# chariot_comms_a.net
KiCad netlist of a schematic drawn in EAGLE
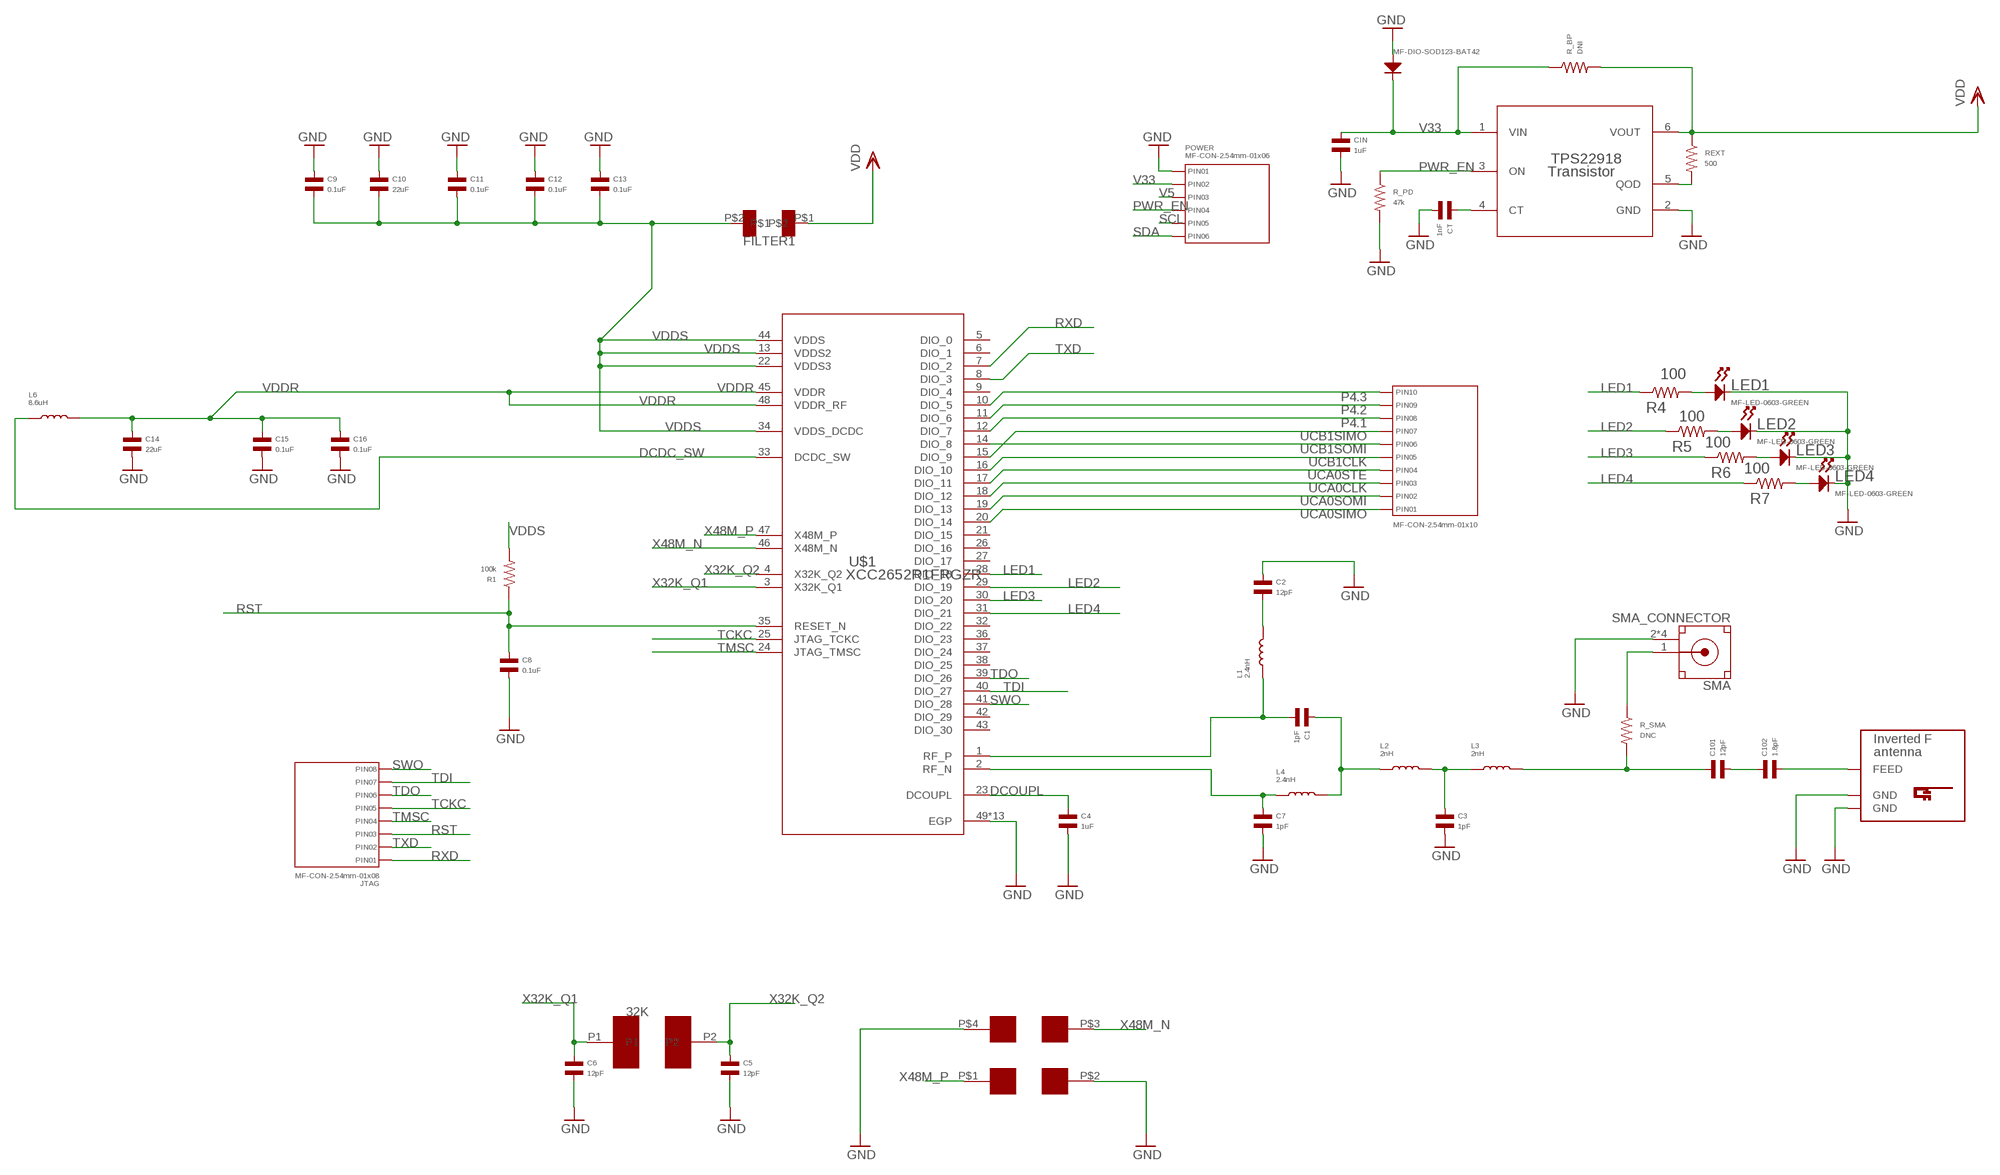
[diagram p0: schematic, sheet 1]

(export (version "E")
  (design (tool "Eeschema 10.0.6"))
  (components
    (comp (ref "32K")
      (value "FC-135")
      (footprint "eagle-import:FC-135")
      (libsource (lib "eagle-import") (part "FC-135"))
    )
    (comp (ref "48M")
      (value "NX2016SA-48M-EXS00A-CS05517")
      (footprint "eagle-import:NX2016SA-48M-EXS00A-CS05517")
      (libsource (lib "eagle-import") (part "NX2016SA-48M-EXS00A-CS05517"))
    )
    (comp (ref "C1")
      (value "1pF")
      (footprint "eagle-import:C0603")
      (libsource (lib "eagle-import") (part "CAPACITOR_NP_0603"))
    )
    (comp (ref "C2")
      (value "12pF")
      (footprint "eagle-import:C0603")
      (libsource (lib "eagle-import") (part "CAPACITOR_NP_0603"))
    )
    (comp (ref "C3")
      (value "1pF")
      (footprint "eagle-import:C0603")
      (libsource (lib "eagle-import") (part "CAPACITOR_NP_0603"))
    )
    (comp (ref "C4")
      (value "1uF")
      (footprint "eagle-import:C0603")
      (libsource (lib "eagle-import") (part "CAPACITOR_NP_0603"))
    )
    (comp (ref "C5")
      (value "12pF")
      (footprint "eagle-import:C0603")
      (libsource (lib "eagle-import") (part "CAPACITOR_NP_0603"))
    )
    (comp (ref "C6")
      (value "12pF")
      (footprint "eagle-import:C0603")
      (libsource (lib "eagle-import") (part "CAPACITOR_NP_0603"))
    )
    (comp (ref "C7")
      (value "1pF")
      (footprint "eagle-import:C0603")
      (libsource (lib "eagle-import") (part "CAPACITOR_NP_0603"))
    )
    (comp (ref "C8")
      (value "0.1uF")
      (footprint "eagle-import:C0603")
      (libsource (lib "eagle-import") (part "CAPACITOR_NP_0603"))
    )
    (comp (ref "C9")
      (value "0.1uF")
      (footprint "eagle-import:C0603")
      (libsource (lib "eagle-import") (part "CAPACITOR_NP_0603"))
    )
    (comp (ref "C10")
      (value "22uF")
      (footprint "eagle-import:C0603")
      (libsource (lib "eagle-import") (part "CAPACITOR_NP_0603"))
    )
    (comp (ref "C11")
      (value "0.1uF")
      (footprint "eagle-import:C0603")
      (libsource (lib "eagle-import") (part "CAPACITOR_NP_0603"))
    )
    (comp (ref "C12")
      (value "0.1uF")
      (footprint "eagle-import:C0603")
      (libsource (lib "eagle-import") (part "CAPACITOR_NP_0603"))
    )
    (comp (ref "C13")
      (value "0.1uF")
      (footprint "eagle-import:C0603")
      (libsource (lib "eagle-import") (part "CAPACITOR_NP_0603"))
    )
    (comp (ref "C14")
      (value "22uF")
      (footprint "eagle-import:C0603")
      (libsource (lib "eagle-import") (part "CAPACITOR_NP_0603"))
    )
    (comp (ref "C15")
      (value "0.1uF")
      (footprint "eagle-import:C0603")
      (libsource (lib "eagle-import") (part "CAPACITOR_NP_0603"))
    )
    (comp (ref "C16")
      (value "0.1uF")
      (footprint "eagle-import:C0603")
      (libsource (lib "eagle-import") (part "CAPACITOR_NP_0603"))
    )
    (comp (ref "C101")
      (value "12pF")
      (footprint "eagle-import:C0603")
      (libsource (lib "eagle-import") (part "CAPACITOR_NP_0603"))
    )
    (comp (ref "C102")
      (value "1.8pF")
      (footprint "eagle-import:C0603")
      (libsource (lib "eagle-import") (part "CAPACITOR_NP_0603"))
    )
    (comp (ref "CIN")
      (value "1uF")
      (footprint "eagle-import:C0603")
      (libsource (lib "eagle-import") (part "CAPACITOR_NP_0603"))
    )
    (comp (ref "COMMS_J")
      (value "MF-CON-2.54mm-01x10")
      (footprint "eagle-import:PTH_2.54MM_01X10")
      (fields (field (name "HOUSEPART") "YES"))
      (libsource (lib "eagle-import") (part "CON_01X10_PTH_2.54MM"))
    )
    (comp (ref "CT")
      (value "1nF")
      (footprint "eagle-import:C0603")
      (libsource (lib "eagle-import") (part "CAPACITOR_NP_0603"))
    )
    (comp (ref "D1")
      (value "MF-DIO-SOD123-BAT42")
      (footprint "eagle-import:SOD-123")
      (fields (field (name "HOUSEPART") "YES"))
      (libsource (lib "eagle-import") (part "DIODES_SOD-123_BAT42"))
    )
    (comp (ref "FILTER1")
      (value "BLM18HE152SN1D")
      (footprint "eagle-import:BLM18HE152SN1D")
      (libsource (lib "eagle-import") (part "BLM18HE152SN1D"))
    )
    (comp (ref "JTAG")
      (value "MF-CON-2.54mm-01x08")
      (footprint "eagle-import:PTH_2.54MM_01X08")
      (fields (field (name "HOUSEPART") "YES"))
      (libsource (lib "eagle-import") (part "CON_01X08_PTH_2.54MM"))
    )
    (comp (ref "L1")
      (value "2.4nH")
      (footprint "eagle-import:L0603")
      (libsource (lib "eagle-import") (part "INDUCTOR_0603"))
    )
    (comp (ref "L2")
      (value "2nH")
      (footprint "eagle-import:L0603")
      (libsource (lib "eagle-import") (part "INDUCTOR_0603"))
    )
    (comp (ref "L3")
      (value "2nH")
      (footprint "eagle-import:L0603")
      (libsource (lib "eagle-import") (part "INDUCTOR_0603"))
    )
    (comp (ref "L4")
      (value "2.4nH")
      (footprint "eagle-import:L0603")
      (libsource (lib "eagle-import") (part "INDUCTOR_0603"))
    )
    (comp (ref "L6")
      (value "8.6uH")
      (footprint "eagle-import:L0603")
      (libsource (lib "eagle-import") (part "INDUCTOR_0603"))
    )
    (comp (ref "LED1")
      (value "MF-LED-0603-GREEN")
      (footprint "eagle-import:LED0603")
      (fields (field (name "HOUSEPART") "YES"))
      (libsource (lib "eagle-import") (part "LED_SINGLE-0603-GREEN"))
    )
    (comp (ref "LED2")
      (value "MF-LED-0603-GREEN")
      (footprint "eagle-import:LED0603")
      (fields (field (name "HOUSEPART") "YES"))
      (libsource (lib "eagle-import") (part "LED_SINGLE-0603-GREEN"))
    )
    (comp (ref "LED3")
      (value "MF-LED-0603-GREEN")
      (footprint "eagle-import:LED0603")
      (fields (field (name "HOUSEPART") "YES"))
      (libsource (lib "eagle-import") (part "LED_SINGLE-0603-GREEN"))
    )
    (comp (ref "LED4")
      (value "MF-LED-0603-GREEN")
      (footprint "eagle-import:LED0603")
      (fields (field (name "HOUSEPART") "YES"))
      (libsource (lib "eagle-import") (part "LED_SINGLE-0603-GREEN"))
    )
    (comp (ref "POWER")
      (value "MF-CON-2.54mm-01x06")
      (footprint "eagle-import:PTH_2.54MM_01X06")
      (fields (field (name "HOUSEPART") "YES"))
      (libsource (lib "eagle-import") (part "CON_01X06_PTH_2.54MM"))
    )
    (comp (ref "R1")
      (value "100k")
      (footprint "eagle-import:R0603")
      (libsource (lib "eagle-import") (part "RESISTOR_0603"))
    )
    (comp (ref "R4")
      (value "100")
      (footprint "eagle-import:R0603")
      (libsource (lib "eagle-import") (part "RESISTOR_0603"))
    )
    (comp (ref "R5")
      (value "100")
      (footprint "eagle-import:R0603")
      (libsource (lib "eagle-import") (part "RESISTOR_0603"))
    )
    (comp (ref "R6")
      (value "100")
      (footprint "eagle-import:R0603")
      (libsource (lib "eagle-import") (part "RESISTOR_0603"))
    )
    (comp (ref "R7")
      (value "100")
      (footprint "eagle-import:R0603")
      (libsource (lib "eagle-import") (part "RESISTOR_0603"))
    )
    (comp (ref "REXT")
      (value "500")
      (footprint "eagle-import:R0603")
      (libsource (lib "eagle-import") (part "RESISTOR_0603"))
    )
    (comp (ref "R_BP")
      (value "DNI")
      (footprint "eagle-import:R0603")
      (libsource (lib "eagle-import") (part "RESISTOR_0603"))
    )
    (comp (ref "R_PD")
      (value "47k")
      (footprint "eagle-import:R0603")
      (libsource (lib "eagle-import") (part "RESISTOR_0603"))
    )
    (comp (ref "R_SMA")
      (value "DNC")
      (footprint "eagle-import:R0603")
      (libsource (lib "eagle-import") (part "RESISTOR_0603"))
    )
    (comp (ref "SMA")
      (value "SMA_CONNECTOR")
      (footprint "eagle-import:LPRS_SMA_CONNECTOR")
      (fields (field (name "MF") "LPRS") (field (name "MP") "SMA CONNECTOR"))
      (libsource (lib "eagle-import") (part "SMA_CONNECTOR"))
    )
    (comp (ref "TPS22918")
      (value "Transistor")
      (footprint "eagle-import:DBV0006A_N")
      (fields (field (name "MANUFACTURER") "Texas Instruments") (field (name "PARTNUMBER") "TPS22918TDBVRQ1"))
      (libsource (lib "eagle-import") (part "TPS22918TDBVRQ1"))
    )
    (comp (ref "U$1")
      (value "XCC2652R1FRGZR")
      (footprint "eagle-import:RGZ0048A")
      (libsource (lib "eagle-import") (part "XCC2652R1FRGZR"))
    )
    (comp (ref "U$2")
      (value "INVERTED_F_ANTENNA+5")
      (footprint "eagle-import:DN007+5")
      (libsource (lib "eagle-import") (part "INVERTED_F_ANTENNA+5"))
    )
  )
  (nets
    (net (code "1") (name "/DCDC_SW") (class "Default")
      (node (ref "L6") (pin "P$1") (pinfunction "P$1_P$1") (pintype "passive"))
      (node (ref "U$1") (pin "33") (pinfunction "DCDC_SW_33") (pintype "power_in"))
    )
    (net (code "2") (name "/DCOUPL") (class "Default")
      (node (ref "C4") (pin "P$1") (pinfunction "P$1_P$1") (pintype "passive"))
      (node (ref "U$1") (pin "23") (pinfunction "DCOUPL_23") (pintype "power_in"))
    )
    (net (code "3") (name "/LED1") (class "Default")
      (node (ref "R4") (pin "P$1") (pinfunction "P$1_P$1") (pintype "passive"))
      (node (ref "U$1") (pin "28") (pinfunction "DIO_18_28") (pintype "bidirectional"))
    )
    (net (code "4") (name "/LED2") (class "Default")
      (node (ref "R5") (pin "P$1") (pinfunction "P$1_P$1") (pintype "passive"))
      (node (ref "U$1") (pin "29") (pinfunction "DIO_19_29") (pintype "bidirectional"))
    )
    (net (code "5") (name "/LED3") (class "Default")
      (node (ref "R6") (pin "P$1") (pinfunction "P$1_P$1") (pintype "passive"))
      (node (ref "U$1") (pin "30") (pinfunction "DIO_20_30") (pintype "bidirectional"))
    )
    (net (code "6") (name "/LED4") (class "Default")
      (node (ref "R7") (pin "P$1") (pinfunction "P$1_P$1") (pintype "passive"))
      (node (ref "U$1") (pin "31") (pinfunction "DIO_21_31") (pintype "bidirectional"))
    )
    (net (code "7") (name "/P4.1") (class "Default")
      (node (ref "COMMS_J") (pin "P$8") (pinfunction "PIN8_P$8") (pintype "bidirectional"))
      (node (ref "U$1") (pin "12") (pinfunction "DIO_7_12") (pintype "bidirectional"))
    )
    (net (code "8") (name "/P4.2") (class "Default")
      (node (ref "COMMS_J") (pin "P$9") (pinfunction "PIN9_P$9") (pintype "bidirectional"))
      (node (ref "U$1") (pin "11") (pinfunction "DIO_6_11") (pintype "bidirectional"))
    )
    (net (code "9") (name "/P4.3") (class "Default")
      (node (ref "COMMS_J") (pin "P$10") (pinfunction "PIN10_P$10") (pintype "bidirectional"))
      (node (ref "U$1") (pin "10") (pinfunction "DIO_5_10") (pintype "bidirectional"))
    )
    (net (code "10") (name "/PWR_EN") (class "Default")
      (node (ref "POWER") (pin "P$4") (pinfunction "PIN4_P$4") (pintype "bidirectional"))
      (node (ref "R_PD") (pin "P$1") (pinfunction "P$1_P$1") (pintype "passive"))
      (node (ref "TPS22918") (pin "3") (pinfunction "ON_3") (pintype "input"))
    )
    (net (code "11") (name "/RST") (class "Default")
      (node (ref "C8") (pin "P$1") (pinfunction "P$1_P$1") (pintype "passive"))
      (node (ref "JTAG") (pin "P$3") (pinfunction "PIN3_P$3") (pintype "bidirectional"))
      (node (ref "R1") (pin "P$1") (pinfunction "P$1_P$1") (pintype "passive"))
      (node (ref "U$1") (pin "35") (pinfunction "RESET_N_35") (pintype "input"))
    )
    (net (code "12") (name "/RXD") (class "Default")
      (node (ref "JTAG") (pin "P$1") (pinfunction "PIN1_P$1") (pintype "bidirectional"))
      (node (ref "U$1") (pin "7") (pinfunction "DIO_2_7") (pintype "bidirectional"))
    )
    (net (code "13") (name "/SCL") (class "Default")
      (node (ref "POWER") (pin "P$5") (pinfunction "PIN5_P$5") (pintype "bidirectional"))
    )
    (net (code "14") (name "/SDA") (class "Default")
      (node (ref "POWER") (pin "P$6") (pinfunction "PIN6_P$6") (pintype "bidirectional"))
    )
    (net (code "15") (name "/SWO") (class "Default")
      (node (ref "JTAG") (pin "P$8") (pinfunction "PIN8_P$8") (pintype "bidirectional"))
      (node (ref "U$1") (pin "41") (pinfunction "DIO_28_41") (pintype "bidirectional"))
    )
    (net (code "16") (name "/TCKC") (class "Default")
      (node (ref "JTAG") (pin "P$5") (pinfunction "PIN5_P$5") (pintype "bidirectional"))
      (node (ref "U$1") (pin "25") (pinfunction "JTAG_TCKC_25") (pintype "bidirectional"))
    )
    (net (code "17") (name "/TDI") (class "Default")
      (node (ref "JTAG") (pin "P$7") (pinfunction "PIN7_P$7") (pintype "bidirectional"))
      (node (ref "U$1") (pin "40") (pinfunction "DIO_27_40") (pintype "bidirectional"))
    )
    (net (code "18") (name "/TDO") (class "Default")
      (node (ref "JTAG") (pin "P$6") (pinfunction "PIN6_P$6") (pintype "bidirectional"))
      (node (ref "U$1") (pin "39") (pinfunction "DIO_26_39") (pintype "bidirectional"))
    )
    (net (code "19") (name "/TMSC") (class "Default")
      (node (ref "JTAG") (pin "P$4") (pinfunction "PIN4_P$4") (pintype "bidirectional"))
      (node (ref "U$1") (pin "24") (pinfunction "JTAG_TMSC_24") (pintype "bidirectional"))
    )
    (net (code "20") (name "/TXD") (class "Default")
      (node (ref "JTAG") (pin "P$2") (pinfunction "PIN2_P$2") (pintype "bidirectional"))
      (node (ref "U$1") (pin "8") (pinfunction "DIO_3_8") (pintype "bidirectional"))
    )
    (net (code "21") (name "/UCA0CLK") (class "Default")
      (node (ref "COMMS_J") (pin "P$3") (pinfunction "PIN3_P$3") (pintype "bidirectional"))
      (node (ref "U$1") (pin "18") (pinfunction "DIO_12_18") (pintype "bidirectional"))
    )
    (net (code "22") (name "/UCA0SIMO") (class "Default")
      (node (ref "COMMS_J") (pin "P$1") (pinfunction "PIN1_P$1") (pintype "bidirectional"))
      (node (ref "U$1") (pin "20") (pinfunction "DIO_14_20") (pintype "bidirectional"))
    )
    (net (code "23") (name "/UCA0SOMI") (class "Default")
      (node (ref "COMMS_J") (pin "P$2") (pinfunction "PIN2_P$2") (pintype "bidirectional"))
      (node (ref "U$1") (pin "19") (pinfunction "DIO_13_19") (pintype "bidirectional"))
    )
    (net (code "24") (name "/UCA0STE") (class "Default")
      (node (ref "COMMS_J") (pin "P$4") (pinfunction "PIN4_P$4") (pintype "bidirectional"))
      (node (ref "U$1") (pin "17") (pinfunction "DIO_11_17") (pintype "bidirectional"))
    )
    (net (code "25") (name "/UCB1CLK") (class "Default")
      (node (ref "COMMS_J") (pin "P$5") (pinfunction "PIN5_P$5") (pintype "bidirectional"))
      (node (ref "U$1") (pin "16") (pinfunction "DIO_10_16") (pintype "bidirectional"))
    )
    (net (code "26") (name "/UCB1SIMO") (class "Default")
      (node (ref "COMMS_J") (pin "P$7") (pinfunction "PIN7_P$7") (pintype "bidirectional"))
      (node (ref "U$1") (pin "15") (pinfunction "DIO_9_15") (pintype "bidirectional"))
    )
    (net (code "27") (name "/UCB1SOMI") (class "Default")
      (node (ref "COMMS_J") (pin "P$6") (pinfunction "PIN6_P$6") (pintype "bidirectional"))
      (node (ref "U$1") (pin "14") (pinfunction "DIO_8_14") (pintype "bidirectional"))
    )
    (net (code "28") (name "/V5") (class "Default")
      (node (ref "POWER") (pin "P$3") (pinfunction "PIN3_P$3") (pintype "bidirectional"))
    )
    (net (code "29") (name "/V33") (class "Default")
      (node (ref "CIN") (pin "P$1") (pinfunction "P$1_P$1") (pintype "passive"))
      (node (ref "D1") (pin "CATHODE") (pinfunction "CATHODE_CATHODE") (pintype "bidirectional"))
      (node (ref "POWER") (pin "P$2") (pinfunction "PIN2_P$2") (pintype "bidirectional"))
      (node (ref "R_BP") (pin "P$1") (pinfunction "P$1_P$1") (pintype "passive"))
      (node (ref "TPS22918") (pin "1") (pinfunction "VIN_1") (pintype "power_in"))
    )
    (net (code "30") (name "/VDDR") (class "Default")
      (node (ref "C14") (pin "P$1") (pinfunction "P$1_P$1") (pintype "passive"))
      (node (ref "C15") (pin "P$1") (pinfunction "P$1_P$1") (pintype "passive"))
      (node (ref "C16") (pin "P$1") (pinfunction "P$1_P$1") (pintype "passive"))
      (node (ref "L6") (pin "P$2") (pinfunction "P$2_P$2") (pintype "passive"))
      (node (ref "U$1") (pin "45") (pinfunction "VDDR_45") (pintype "power_in"))
      (node (ref "U$1") (pin "48") (pinfunction "VDDR_RF_48") (pintype "power_in"))
    )
    (net (code "31") (name "/VDDS") (class "Default")
      (node (ref "C10") (pin "P$2") (pinfunction "P$2_P$2") (pintype "passive"))
      (node (ref "C11") (pin "P$2") (pinfunction "P$2_P$2") (pintype "passive"))
      (node (ref "C12") (pin "P$2") (pinfunction "P$2_P$2") (pintype "passive"))
      (node (ref "C13") (pin "P$2") (pinfunction "P$2_P$2") (pintype "passive"))
      (node (ref "C9") (pin "P$2") (pinfunction "P$2_P$2") (pintype "passive"))
      (node (ref "FILTER1") (pin "P$2") (pinfunction "P$2_P$2") (pintype "bidirectional"))
      (node (ref "R1") (pin "P$2") (pinfunction "P$2_P$2") (pintype "passive"))
      (node (ref "U$1") (pin "13") (pinfunction "VDDS2_13") (pintype "power_in"))
      (node (ref "U$1") (pin "22") (pinfunction "VDDS3_22") (pintype "power_in"))
      (node (ref "U$1") (pin "34") (pinfunction "VDDS_DCDC_34") (pintype "power_in"))
      (node (ref "U$1") (pin "44") (pinfunction "VDDS_44") (pintype "power_in"))
    )
    (net (code "32") (name "/X32K_Q1") (class "Default")
      (node (ref "32K") (pin "P1") (pinfunction "P1_P1") (pintype "bidirectional"))
      (node (ref "C6") (pin "P$1") (pinfunction "P$1_P$1") (pintype "passive"))
      (node (ref "U$1") (pin "3") (pinfunction "X32K_Q1_3") (pintype "bidirectional"))
    )
    (net (code "33") (name "/X32K_Q2") (class "Default")
      (node (ref "32K") (pin "P2") (pinfunction "P2_P2") (pintype "bidirectional"))
      (node (ref "C5") (pin "P$1") (pinfunction "P$1_P$1") (pintype "passive"))
      (node (ref "U$1") (pin "4") (pinfunction "X32K_Q2_4") (pintype "bidirectional"))
    )
    (net (code "34") (name "/X48M_N") (class "Default")
      (node (ref "48M") (pin "P$3") (pinfunction "P$3_P$3") (pintype "bidirectional"))
      (node (ref "U$1") (pin "46") (pinfunction "X48M_N_46") (pintype "bidirectional"))
    )
    (net (code "35") (name "/X48M_P") (class "Default")
      (node (ref "48M") (pin "P$1") (pinfunction "P$1_P$1") (pintype "bidirectional"))
      (node (ref "U$1") (pin "47") (pinfunction "X48M_P_47") (pintype "bidirectional"))
    )
    (net (code "36") (name "GND") (class "Default")
      (node (ref "48M") (pin "P$2") (pinfunction "P$2_P$2") (pintype "bidirectional"))
      (node (ref "48M") (pin "P$4") (pinfunction "P$4_P$4") (pintype "bidirectional"))
      (node (ref "C10") (pin "P$1") (pinfunction "P$1_P$1") (pintype "passive"))
      (node (ref "C11") (pin "P$1") (pinfunction "P$1_P$1") (pintype "passive"))
      (node (ref "C12") (pin "P$1") (pinfunction "P$1_P$1") (pintype "passive"))
      (node (ref "C13") (pin "P$1") (pinfunction "P$1_P$1") (pintype "passive"))
      (node (ref "C14") (pin "P$2") (pinfunction "P$2_P$2") (pintype "passive"))
      (node (ref "C15") (pin "P$2") (pinfunction "P$2_P$2") (pintype "passive"))
      (node (ref "C16") (pin "P$2") (pinfunction "P$2_P$2") (pintype "passive"))
      (node (ref "C2") (pin "P$1") (pinfunction "P$1_P$1") (pintype "passive"))
      (node (ref "C3") (pin "P$2") (pinfunction "P$2_P$2") (pintype "passive"))
      (node (ref "C4") (pin "P$2") (pinfunction "P$2_P$2") (pintype "passive"))
      (node (ref "C5") (pin "P$2") (pinfunction "P$2_P$2") (pintype "passive"))
      (node (ref "C6") (pin "P$2") (pinfunction "P$2_P$2") (pintype "passive"))
      (node (ref "C7") (pin "P$2") (pinfunction "P$2_P$2") (pintype "passive"))
      (node (ref "C8") (pin "P$2") (pinfunction "P$2_P$2") (pintype "passive"))
      (node (ref "C9") (pin "P$1") (pinfunction "P$1_P$1") (pintype "passive"))
      (node (ref "CIN") (pin "P$2") (pinfunction "P$2_P$2") (pintype "passive"))
      (node (ref "CT") (pin "P$2") (pinfunction "P$2_P$2") (pintype "passive"))
      (node (ref "D1") (pin "ANODE") (pinfunction "ANODE_ANODE") (pintype "bidirectional"))
      (node (ref "LED1") (pin "CATHODE") (pinfunction "CATHODE_CATHODE") (pintype "power_in"))
      (node (ref "LED2") (pin "CATHODE") (pinfunction "CATHODE_CATHODE") (pintype "power_in"))
      (node (ref "LED3") (pin "CATHODE") (pinfunction "CATHODE_CATHODE") (pintype "power_in"))
      (node (ref "LED4") (pin "CATHODE") (pinfunction "CATHODE_CATHODE") (pintype "power_in"))
      (node (ref "POWER") (pin "P$1") (pinfunction "PIN1_P$1") (pintype "bidirectional"))
      (node (ref "R_PD") (pin "P$2") (pinfunction "P$2_P$2") (pintype "passive"))
      (node (ref "SMA") (pin "2") (pinfunction "GND_2") (pintype "passive"))
      (node (ref "SMA") (pin "3") (pinfunction "GND_3") (pintype "passive"))
      (node (ref "SMA") (pin "4") (pinfunction "GND_4") (pintype "passive"))
      (node (ref "SMA") (pin "5") (pinfunction "GND_5") (pintype "passive"))
      (node (ref "TPS22918") (pin "2") (pinfunction "GND_2") (pintype "power_in"))
      (node (ref "U$1") (pin "49") (pinfunction "EGP_49") (pintype "power_in"))
      (node (ref "U$1") (pin "V1") (pinfunction "EGP_V1") (pintype "power_in"))
      (node (ref "U$1") (pin "V10") (pinfunction "EGP_V10") (pintype "power_in"))
      (node (ref "U$1") (pin "V11") (pinfunction "EGP_V11") (pintype "power_in"))
      (node (ref "U$1") (pin "V12") (pinfunction "EGP_V12") (pintype "power_in"))
      (node (ref "U$1") (pin "V2") (pinfunction "EGP_V2") (pintype "power_in"))
      (node (ref "U$1") (pin "V3") (pinfunction "EGP_V3") (pintype "power_in"))
      (node (ref "U$1") (pin "V4") (pinfunction "EGP_V4") (pintype "power_in"))
      (node (ref "U$1") (pin "V5") (pinfunction "EGP_V5") (pintype "power_in"))
      (node (ref "U$1") (pin "V6") (pinfunction "EGP_V6") (pintype "power_in"))
      (node (ref "U$1") (pin "V7") (pinfunction "EGP_V7") (pintype "power_in"))
      (node (ref "U$1") (pin "V8") (pinfunction "EGP_V8") (pintype "power_in"))
      (node (ref "U$1") (pin "V9") (pinfunction "EGP_V9") (pintype "power_in"))
      (node (ref "U$2") (pin "GND") (pinfunction "GND_GND") (pintype "bidirectional"))
      (node (ref "U$2") (pin "GND@1") (pinfunction "GND_GND@1") (pintype "bidirectional"))
    )
    (net (code "37") (name "Net-(C1-PadP$1)") (class "Default")
      (node (ref "C1") (pin "P$1") (pinfunction "P$1_P$1") (pintype "passive"))
      (node (ref "L2") (pin "P$1") (pinfunction "P$1_P$1") (pintype "passive"))
      (node (ref "L4") (pin "P$2") (pinfunction "P$2_P$2") (pintype "passive"))
    )
    (net (code "38") (name "Net-(C2-PadP$2)") (class "Default")
      (node (ref "C2") (pin "P$2") (pinfunction "P$2_P$2") (pintype "passive"))
      (node (ref "L1") (pin "P$2") (pinfunction "P$2_P$2") (pintype "passive"))
    )
    (net (code "39") (name "Net-(C3-PadP$1)") (class "Default")
      (node (ref "C3") (pin "P$1") (pinfunction "P$1_P$1") (pintype "passive"))
      (node (ref "L2") (pin "P$2") (pinfunction "P$2_P$2") (pintype "passive"))
      (node (ref "L3") (pin "P$1") (pinfunction "P$1_P$1") (pintype "passive"))
    )
    (net (code "40") (name "Net-(C101-PadP$1)") (class "Default")
      (node (ref "C101") (pin "P$1") (pinfunction "P$1_P$1") (pintype "passive"))
      (node (ref "L3") (pin "P$2") (pinfunction "P$2_P$2") (pintype "passive"))
      (node (ref "R_SMA") (pin "P$2") (pinfunction "P$2_P$2") (pintype "passive"))
    )
    (net (code "41") (name "Net-(C101-PadP$2)") (class "Default")
      (node (ref "C101") (pin "P$2") (pinfunction "P$2_P$2") (pintype "passive"))
      (node (ref "C102") (pin "P$1") (pinfunction "P$1_P$1") (pintype "passive"))
    )
    (net (code "42") (name "Net-(C102-PadP$2)") (class "Default")
      (node (ref "C102") (pin "P$2") (pinfunction "P$2_P$2") (pintype "passive"))
      (node (ref "U$2") (pin "FEED") (pinfunction "FEED_FEED") (pintype "bidirectional"))
    )
    (net (code "43") (name "Net-(LED1-PadANODE)") (class "Default")
      (node (ref "LED1") (pin "ANODE") (pinfunction "ANODE_ANODE") (pintype "power_in"))
      (node (ref "R4") (pin "P$2") (pinfunction "P$2_P$2") (pintype "passive"))
    )
    (net (code "44") (name "Net-(LED2-PadANODE)") (class "Default")
      (node (ref "LED2") (pin "ANODE") (pinfunction "ANODE_ANODE") (pintype "power_in"))
      (node (ref "R5") (pin "P$2") (pinfunction "P$2_P$2") (pintype "passive"))
    )
    (net (code "45") (name "Net-(LED3-PadANODE)") (class "Default")
      (node (ref "LED3") (pin "ANODE") (pinfunction "ANODE_ANODE") (pintype "power_in"))
      (node (ref "R6") (pin "P$2") (pinfunction "P$2_P$2") (pintype "passive"))
    )
    (net (code "46") (name "Net-(LED4-PadANODE)") (class "Default")
      (node (ref "LED4") (pin "ANODE") (pinfunction "ANODE_ANODE") (pintype "power_in"))
      (node (ref "R7") (pin "P$2") (pinfunction "P$2_P$2") (pintype "passive"))
    )
    (net (code "47") (name "Net-(SMA-SIG)") (class "Default")
      (node (ref "R_SMA") (pin "P$1") (pinfunction "P$1_P$1") (pintype "passive"))
      (node (ref "SMA") (pin "1") (pinfunction "SIG_1") (pintype "passive"))
    )
    (net (code "48") (name "Net-(TPS22918-CT)") (class "Default")
      (node (ref "CT") (pin "P$1") (pinfunction "P$1_P$1") (pintype "passive"))
      (node (ref "TPS22918") (pin "4") (pinfunction "CT_4") (pintype "output"))
    )
    (net (code "49") (name "Net-(TPS22918-QOD)") (class "Default")
      (node (ref "REXT") (pin "P$2") (pinfunction "P$2_P$2") (pintype "passive"))
      (node (ref "TPS22918") (pin "5") (pinfunction "QOD_5") (pintype "input"))
    )
    (net (code "50") (name "Net-(U$1-RF_N)") (class "Default")
      (node (ref "C7") (pin "P$1") (pinfunction "P$1_P$1") (pintype "passive"))
      (node (ref "L4") (pin "P$1") (pinfunction "P$1_P$1") (pintype "passive"))
      (node (ref "U$1") (pin "2") (pinfunction "RF_N_2") (pintype "bidirectional"))
    )
    (net (code "51") (name "Net-(U$1-RF_P)") (class "Default")
      (node (ref "C1") (pin "P$2") (pinfunction "P$2_P$2") (pintype "passive"))
      (node (ref "L1") (pin "P$1") (pinfunction "P$1_P$1") (pintype "passive"))
      (node (ref "U$1") (pin "1") (pinfunction "RF_P_1") (pintype "bidirectional"))
    )
    (net (code "52") (name "VDD") (class "Default")
      (node (ref "FILTER1") (pin "P$1") (pinfunction "P$1_P$1") (pintype "bidirectional"))
      (node (ref "REXT") (pin "P$1") (pinfunction "P$1_P$1") (pintype "passive"))
      (node (ref "R_BP") (pin "P$2") (pinfunction "P$2_P$2") (pintype "passive"))
      (node (ref "TPS22918") (pin "6") (pinfunction "VOUT_6") (pintype "power_in"))
    )
    (net (code "53") (name "unconnected-(U$1-DIO_0-Pad5)") (class "Default")
      (node (ref "U$1") (pin "5") (pinfunction "DIO_0_5") (pintype "bidirectional"))
    )
    (net (code "54") (name "unconnected-(U$1-DIO_1-Pad6)") (class "Default")
      (node (ref "U$1") (pin "6") (pinfunction "DIO_1_6") (pintype "bidirectional"))
    )
    (net (code "55") (name "unconnected-(U$1-DIO_4-Pad9)") (class "Default")
      (node (ref "U$1") (pin "9") (pinfunction "DIO_4_9") (pintype "bidirectional"))
    )
    (net (code "56") (name "unconnected-(U$1-DIO_15-Pad21)") (class "Default")
      (node (ref "U$1") (pin "21") (pinfunction "DIO_15_21") (pintype "bidirectional"))
    )
    (net (code "57") (name "unconnected-(U$1-DIO_16-Pad26)") (class "Default")
      (node (ref "U$1") (pin "26") (pinfunction "DIO_16_26") (pintype "bidirectional"))
    )
    (net (code "58") (name "unconnected-(U$1-DIO_17-Pad27)") (class "Default")
      (node (ref "U$1") (pin "27") (pinfunction "DIO_17_27") (pintype "bidirectional"))
    )
    (net (code "59") (name "unconnected-(U$1-DIO_22-Pad32)") (class "Default")
      (node (ref "U$1") (pin "32") (pinfunction "DIO_22_32") (pintype "bidirectional"))
    )
    (net (code "60") (name "unconnected-(U$1-DIO_23-Pad36)") (class "Default")
      (node (ref "U$1") (pin "36") (pinfunction "DIO_23_36") (pintype "bidirectional"))
    )
    (net (code "61") (name "unconnected-(U$1-DIO_24-Pad37)") (class "Default")
      (node (ref "U$1") (pin "37") (pinfunction "DIO_24_37") (pintype "bidirectional"))
    )
    (net (code "62") (name "unconnected-(U$1-DIO_25-Pad38)") (class "Default")
      (node (ref "U$1") (pin "38") (pinfunction "DIO_25_38") (pintype "bidirectional"))
    )
    (net (code "63") (name "unconnected-(U$1-DIO_29-Pad42)") (class "Default")
      (node (ref "U$1") (pin "42") (pinfunction "DIO_29_42") (pintype "bidirectional"))
    )
    (net (code "64") (name "unconnected-(U$1-DIO_30-Pad43)") (class "Default")
      (node (ref "U$1") (pin "43") (pinfunction "DIO_30_43") (pintype "bidirectional"))
    )
  )
)
